# Sheet1.net
KiCad netlist of a schematic drawn in Altium Designer
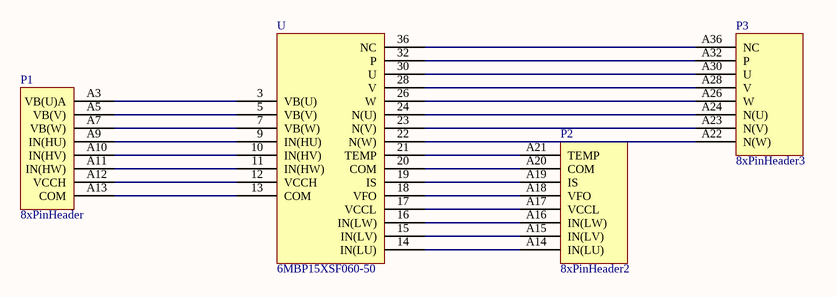
[diagram p0: Sheet1.SchDoc]

(export (version "E")
  (design (tool "Eeschema 10.0.6"))
  (components
    (comp (ref "P1")
      (value "8xPinHeader")
      (footprint "8xPinHeader")
      (libsource (lib "Schlib1") (part "8xPinHeader"))
    )
    (comp (ref "P2")
      (value "8xPinHeader2")
      (footprint "8xPİNHEADER2")
      (libsource (lib "Schlib1") (part "8xPinHeader2"))
    )
    (comp (ref "P3")
      (value "8xPinHeader3")
      (footprint "8xPİNHEADER3")
      (libsource (lib "Schlib1") (part "8xPinHeader3"))
    )
    (comp (ref "U")
      (value "6MBP15XSF060-50")
      (footprint "6MBP15XSF060-50")
      (description "600v 15a")
      (libsource (lib "Schlib1") (part "6MBP15XSF060-50"))
    )
  )
  (nets
    (net (code "1") (name "Net-(P1-COM)") (class "Default")
      (node (ref "P1") (pin "A13") (pinfunction "COM_A13") (pintype "passive"))
      (node (ref "U") (pin "13") (pinfunction "COM_13") (pintype "passive"))
    )
    (net (code "2") (name "Net-(P1-IN(HU))") (class "Default")
      (node (ref "P1") (pin "A9") (pinfunction "IN(HU)_A9") (pintype "passive"))
      (node (ref "U") (pin "9") (pinfunction "IN(HU)_9") (pintype "passive"))
    )
    (net (code "3") (name "Net-(P1-IN(HV))") (class "Default")
      (node (ref "P1") (pin "A10") (pinfunction "IN(HV)_A10") (pintype "passive"))
      (node (ref "U") (pin "10") (pinfunction "IN(HV)_10") (pintype "passive"))
    )
    (net (code "4") (name "Net-(P1-IN(HW))") (class "Default")
      (node (ref "P1") (pin "A11") (pinfunction "IN(HW)_A11") (pintype "passive"))
      (node (ref "U") (pin "11") (pinfunction "IN(HW)_11") (pintype "passive"))
    )
    (net (code "5") (name "Net-(P1-VB(U)A)") (class "Default")
      (node (ref "P1") (pin "A3") (pinfunction "VB(U)A_A3") (pintype "passive"))
      (node (ref "U") (pin "3") (pinfunction "VB(U)_3") (pintype "passive"))
    )
    (net (code "6") (name "Net-(P1-VB(V))") (class "Default")
      (node (ref "P1") (pin "A5") (pinfunction "VB(V)_A5") (pintype "passive"))
      (node (ref "U") (pin "5") (pinfunction "VB(V)_5") (pintype "passive"))
    )
    (net (code "7") (name "Net-(P1-VB(W))") (class "Default")
      (node (ref "P1") (pin "A7") (pinfunction "VB(W)_A7") (pintype "passive"))
      (node (ref "U") (pin "7") (pinfunction "VB(W)_7") (pintype "passive"))
    )
    (net (code "8") (name "Net-(P1-VCCH)") (class "Default")
      (node (ref "P1") (pin "A12") (pinfunction "VCCH_A12") (pintype "passive"))
      (node (ref "U") (pin "12") (pinfunction "VCCH_12") (pintype "passive"))
    )
    (net (code "9") (name "Net-(P2-COM)") (class "Default")
      (node (ref "P2") (pin "A20") (pinfunction "COM_A20") (pintype "passive"))
      (node (ref "U") (pin "20") (pinfunction "COM_20") (pintype "passive"))
    )
    (net (code "10") (name "Net-(P2-IN(LU))") (class "Default")
      (node (ref "P2") (pin "A14") (pinfunction "IN(LU)_A14") (pintype "passive"))
      (node (ref "U") (pin "14") (pinfunction "IN(LU)_14") (pintype "passive"))
    )
    (net (code "11") (name "Net-(P2-IN(LV))") (class "Default")
      (node (ref "P2") (pin "A15") (pinfunction "IN(LV)_A15") (pintype "passive"))
      (node (ref "U") (pin "15") (pinfunction "IN(LV)_15") (pintype "passive"))
    )
    (net (code "12") (name "Net-(P2-IN(LW))") (class "Default")
      (node (ref "P2") (pin "A16") (pinfunction "IN(LW)_A16") (pintype "passive"))
      (node (ref "U") (pin "16") (pinfunction "IN(LW)_16") (pintype "passive"))
    )
    (net (code "13") (name "Net-(P2-IS)") (class "Default")
      (node (ref "P2") (pin "A19") (pinfunction "IS_A19") (pintype "passive"))
      (node (ref "U") (pin "19") (pinfunction "IS_19") (pintype "passive"))
    )
    (net (code "14") (name "Net-(P2-TEMP)") (class "Default")
      (node (ref "P2") (pin "A21") (pinfunction "TEMP_A21") (pintype "passive"))
      (node (ref "U") (pin "21") (pinfunction "TEMP_21") (pintype "passive"))
    )
    (net (code "15") (name "Net-(P2-VCCL)") (class "Default")
      (node (ref "P2") (pin "A17") (pinfunction "VCCL_A17") (pintype "passive"))
      (node (ref "U") (pin "17") (pinfunction "VCCL_17") (pintype "passive"))
    )
    (net (code "16") (name "Net-(P2-VFO)") (class "Default")
      (node (ref "P2") (pin "A18") (pinfunction "VFO_A18") (pintype "passive"))
      (node (ref "U") (pin "18") (pinfunction "VFO_18") (pintype "passive"))
    )
    (net (code "17") (name "Net-(P3-N(U))") (class "Default")
      (node (ref "P3") (pin "A24") (pinfunction "N(U)_A24") (pintype "passive"))
      (node (ref "U") (pin "24") (pinfunction "N(U)_24") (pintype "passive"))
    )
    (net (code "18") (name "Net-(P3-N(V))") (class "Default")
      (node (ref "P3") (pin "A23") (pinfunction "N(V)_A23") (pintype "passive"))
      (node (ref "U") (pin "23") (pinfunction "N(V)_23") (pintype "passive"))
    )
    (net (code "19") (name "Net-(P3-N(W))") (class "Default")
      (node (ref "P3") (pin "A22") (pinfunction "N(W)_A22") (pintype "passive"))
      (node (ref "U") (pin "22") (pinfunction "N(W)_22") (pintype "passive"))
    )
    (net (code "20") (name "Net-(P3-NC)") (class "Default")
      (node (ref "P3") (pin "A36") (pinfunction "NC_A36") (pintype "passive"))
      (node (ref "U") (pin "36") (pinfunction "NC_36") (pintype "passive"))
    )
    (net (code "21") (name "Net-(P3-P)") (class "Default")
      (node (ref "P3") (pin "A32") (pinfunction "P_A32") (pintype "passive"))
      (node (ref "U") (pin "32") (pinfunction "P_32") (pintype "passive"))
    )
    (net (code "22") (name "Net-(P3-U)") (class "Default")
      (node (ref "P3") (pin "A30") (pinfunction "U_A30") (pintype "passive"))
      (node (ref "U") (pin "30") (pinfunction "U_30") (pintype "passive"))
    )
    (net (code "23") (name "Net-(P3-V)") (class "Default")
      (node (ref "P3") (pin "A28") (pinfunction "V_A28") (pintype "passive"))
      (node (ref "U") (pin "28") (pinfunction "V_28") (pintype "passive"))
    )
    (net (code "24") (name "Net-(P3-W)") (class "Default")
      (node (ref "P3") (pin "A26") (pinfunction "W_A26") (pintype "passive"))
      (node (ref "U") (pin "26") (pinfunction "W_26") (pintype "passive"))
    )
  )
)
